# ButtonMatrix.net
KiCad netlist of a schematic drawn in EAGLE
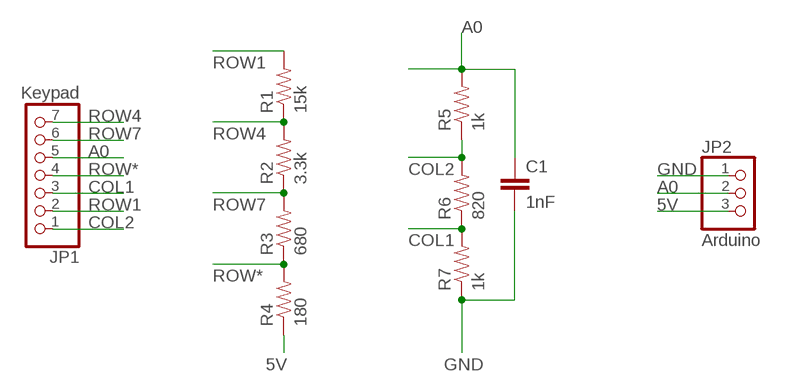
[diagram p0: schematic, sheet 1]

(export (version "E")
  (design (tool "Eeschema 10.0.6"))
  (components
    (comp (ref "C1")
      (value "1nF")
      (footprint "eagle-import:CAP-PTH-SMALL")
      (libsource (lib "eagle-import") (part "CAPPTH"))
    )
    (comp (ref "JP1")
      (value "Keypad")
      (footprint "eagle-import:1X07")
      (libsource (lib "eagle-import") (part "PINHD-1X7"))
    )
    (comp (ref "JP2")
      (value "Arduino")
      (footprint "eagle-import:1X03")
      (libsource (lib "eagle-import") (part "PINHD-1X3"))
    )
    (comp (ref "R1")
      (value "15k")
      (footprint "eagle-import:AXIAL-0.5")
      (libsource (lib "eagle-import") (part "RESISTORPTH-1/2W"))
    )
    (comp (ref "R2")
      (value "3.3k")
      (footprint "eagle-import:AXIAL-0.5")
      (libsource (lib "eagle-import") (part "RESISTORPTH-1/2W"))
    )
    (comp (ref "R3")
      (value "680")
      (footprint "eagle-import:AXIAL-0.5")
      (libsource (lib "eagle-import") (part "RESISTORPTH-1/2W"))
    )
    (comp (ref "R4")
      (value "180")
      (footprint "eagle-import:AXIAL-0.5")
      (libsource (lib "eagle-import") (part "RESISTORPTH-1/2W"))
    )
    (comp (ref "R5")
      (value "1k")
      (footprint "eagle-import:AXIAL-0.5")
      (libsource (lib "eagle-import") (part "RESISTORPTH-1/2W"))
    )
    (comp (ref "R6")
      (value "820")
      (footprint "eagle-import:AXIAL-0.5")
      (libsource (lib "eagle-import") (part "RESISTORPTH-1/2W"))
    )
    (comp (ref "R7")
      (value "1k")
      (footprint "eagle-import:AXIAL-0.5")
      (libsource (lib "eagle-import") (part "RESISTORPTH-1/2W"))
    )
  )
  (nets
    (net (code "1") (name "/5V") (class "Default")
      (node (ref "JP2") (pin "3") (pinfunction "3_3") (pintype "passive"))
      (node (ref "R4") (pin "P$1") (pinfunction "1_P$1") (pintype "passive"))
    )
    (net (code "2") (name "/A0") (class "Default")
      (node (ref "C1") (pin "1") (pinfunction "1_1") (pintype "passive"))
      (node (ref "JP1") (pin "5") (pinfunction "5_5") (pintype "passive"))
      (node (ref "JP2") (pin "2") (pinfunction "2_2") (pintype "passive"))
      (node (ref "R5") (pin "P$2") (pinfunction "2_P$2") (pintype "passive"))
    )
    (net (code "3") (name "/COL1") (class "Default")
      (node (ref "JP1") (pin "3") (pinfunction "3_3") (pintype "passive"))
      (node (ref "R6") (pin "P$1") (pinfunction "1_P$1") (pintype "passive"))
      (node (ref "R7") (pin "P$2") (pinfunction "2_P$2") (pintype "passive"))
    )
    (net (code "4") (name "/COL2") (class "Default")
      (node (ref "JP1") (pin "1") (pinfunction "1_1") (pintype "passive"))
      (node (ref "R5") (pin "P$1") (pinfunction "1_P$1") (pintype "passive"))
      (node (ref "R6") (pin "P$2") (pinfunction "2_P$2") (pintype "passive"))
    )
    (net (code "5") (name "/GND") (class "Default")
      (node (ref "C1") (pin "2") (pinfunction "2_2") (pintype "passive"))
      (node (ref "JP2") (pin "1") (pinfunction "1_1") (pintype "passive"))
      (node (ref "R7") (pin "P$1") (pinfunction "1_P$1") (pintype "passive"))
    )
    (net (code "6") (name "/ROW*") (class "Default")
      (node (ref "JP1") (pin "4") (pinfunction "4_4") (pintype "passive"))
      (node (ref "R3") (pin "P$1") (pinfunction "1_P$1") (pintype "passive"))
      (node (ref "R4") (pin "P$2") (pinfunction "2_P$2") (pintype "passive"))
    )
    (net (code "7") (name "/ROW1") (class "Default")
      (node (ref "JP1") (pin "2") (pinfunction "2_2") (pintype "passive"))
      (node (ref "R1") (pin "P$2") (pinfunction "2_P$2") (pintype "passive"))
    )
    (net (code "8") (name "/ROW4") (class "Default")
      (node (ref "JP1") (pin "7") (pinfunction "7_7") (pintype "passive"))
      (node (ref "R1") (pin "P$1") (pinfunction "1_P$1") (pintype "passive"))
      (node (ref "R2") (pin "P$2") (pinfunction "2_P$2") (pintype "passive"))
    )
    (net (code "9") (name "/ROW7") (class "Default")
      (node (ref "JP1") (pin "6") (pinfunction "6_6") (pintype "passive"))
      (node (ref "R2") (pin "P$1") (pinfunction "1_P$1") (pintype "passive"))
      (node (ref "R3") (pin "P$2") (pinfunction "2_P$2") (pintype "passive"))
    )
  )
)
